# IoT_Week_7.net
KiCad netlist of a schematic drawn in EAGLE
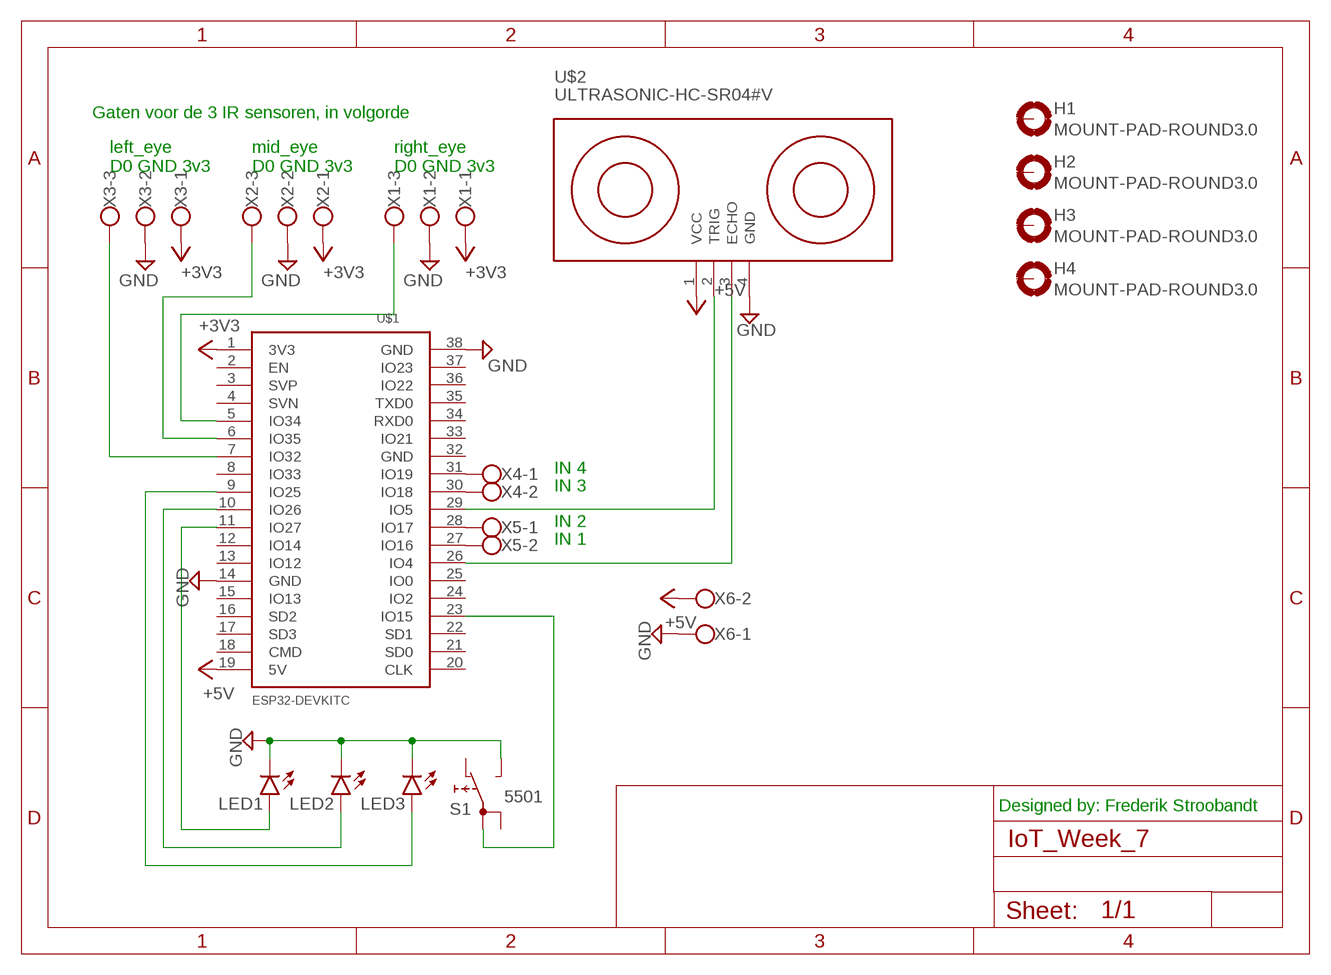
[diagram p0: schematic, sheet 1]

(export (version "E")
  (design (tool "Eeschema 10.0.6"))
  (components
    (comp (ref "H1")
      (value "MOUNT-PAD-ROUND3.0")
      (footprint "eagle-import:3,0-PAD")
      (libsource (lib "eagle-import") (part "MOUNT-PAD-ROUND3.0"))
    )
    (comp (ref "H2")
      (value "MOUNT-PAD-ROUND3.0")
      (footprint "eagle-import:3,0-PAD")
      (libsource (lib "eagle-import") (part "MOUNT-PAD-ROUND3.0"))
    )
    (comp (ref "H3")
      (value "MOUNT-PAD-ROUND3.0")
      (footprint "eagle-import:3,0-PAD")
      (libsource (lib "eagle-import") (part "MOUNT-PAD-ROUND3.0"))
    )
    (comp (ref "H4")
      (value "MOUNT-PAD-ROUND3.0")
      (footprint "eagle-import:3,0-PAD")
      (libsource (lib "eagle-import") (part "MOUNT-PAD-ROUND3.0"))
    )
    (comp (ref "LED1")
      (value "LAP4-BOTTOM")
      (footprint "eagle-import:P47F-BOTTOM")
      (libsource (lib "eagle-import") (part "P4-BOTTOMLA"))
    )
    (comp (ref "LED2")
      (value "LAP4-BOTTOM")
      (footprint "eagle-import:P47F-BOTTOM")
      (libsource (lib "eagle-import") (part "P4-BOTTOMLA"))
    )
    (comp (ref "LED3")
      (value "LAP4-BOTTOM")
      (footprint "eagle-import:P47F-BOTTOM")
      (libsource (lib "eagle-import") (part "P4-BOTTOMLA"))
    )
    (comp (ref "S1")
      (value "5501")
      (footprint "eagle-import:5501")
      (libsource (lib "eagle-import") (part "55?01"))
    )
    (comp (ref "U$1")
      (value "ESP32DEVKITC")
      (footprint "eagle-import:ESP32-DEVKITC")
      (libsource (lib "eagle-import") (part "ESP32DEVKITC"))
    )
    (comp (ref "U$2")
      (value "ULTRASONIC-HC-SR04#V")
      (footprint "eagle-import:ULTRASONIC-HC-SR04#V")
      (libsource (lib "eagle-import") (part "ULTRASONIC-HC-SR04#V"))
    )
    (comp (ref "X1")
      (value "W237-103")
      (footprint "eagle-import:W237-103")
      (fields (field (name "MPN") "237-103"))
      (libsource (lib "eagle-import") (part "W237-103"))
    )
    (comp (ref "X2")
      (value "W237-103")
      (footprint "eagle-import:W237-103")
      (fields (field (name "MPN") "237-103"))
      (libsource (lib "eagle-import") (part "W237-103"))
    )
    (comp (ref "X3")
      (value "W237-103")
      (footprint "eagle-import:W237-103")
      (fields (field (name "MPN") "237-103"))
      (libsource (lib "eagle-import") (part "W237-103"))
    )
    (comp (ref "X4")
      (value "W237-102")
      (footprint "eagle-import:W237-102")
      (fields (field (name "MPN") "237-102"))
      (libsource (lib "eagle-import") (part "W237-102"))
    )
    (comp (ref "X5")
      (value "W237-102")
      (footprint "eagle-import:W237-102")
      (fields (field (name "MPN") "237-102"))
      (libsource (lib "eagle-import") (part "W237-102"))
    )
    (comp (ref "X6")
      (value "W237-102")
      (footprint "eagle-import:W237-102")
      (fields (field (name "MPN") "237-102"))
      (libsource (lib "eagle-import") (part "W237-102"))
    )
  )
  (nets
    (net (code "1") (name "+3V3") (class "Default")
      (node (ref "U$1") (pin "1") (pinfunction "3V3_1") (pintype "bidirectional"))
      (node (ref "X1") (pin "1") (pinfunction "KL_1") (pintype "passive"))
      (node (ref "X2") (pin "1") (pinfunction "KL_1") (pintype "passive"))
      (node (ref "X3") (pin "1") (pinfunction "KL_1") (pintype "passive"))
    )
    (net (code "2") (name "+5V") (class "Default")
      (node (ref "U$1") (pin "19") (pinfunction "5V_19") (pintype "bidirectional"))
      (node (ref "U$2") (pin "1") (pinfunction "VCC_1") (pintype "power_in"))
      (node (ref "X6") (pin "2") (pinfunction "KL_2") (pintype "passive"))
    )
    (net (code "3") (name "GND") (class "Default")
      (node (ref "LED1") (pin "C") (pinfunction "C_C") (pintype "passive"))
      (node (ref "LED2") (pin "C") (pinfunction "C_C") (pintype "passive"))
      (node (ref "LED3") (pin "C") (pinfunction "C_C") (pintype "passive"))
      (node (ref "S1") (pin "NO") (pinfunction "NO_NO") (pintype "passive"))
      (node (ref "U$1") (pin "14") (pinfunction "GND_14") (pintype "bidirectional"))
      (node (ref "U$1") (pin "38") (pinfunction "GND_38") (pintype "bidirectional"))
      (node (ref "U$2") (pin "4") (pinfunction "GND_4") (pintype "power_in"))
      (node (ref "X1") (pin "2") (pinfunction "KL_2") (pintype "passive"))
      (node (ref "X2") (pin "2") (pinfunction "KL_2") (pintype "passive"))
      (node (ref "X3") (pin "2") (pinfunction "KL_2") (pintype "passive"))
      (node (ref "X6") (pin "1") (pinfunction "KL_1") (pintype "passive"))
    )
    (net (code "4") (name "Net-(U$1-IO4)") (class "Default")
      (node (ref "U$1") (pin "26") (pinfunction "IO4_26") (pintype "bidirectional"))
      (node (ref "U$2") (pin "3") (pinfunction "ECHO_3") (pintype "output"))
    )
    (net (code "5") (name "Net-(U$1-IO5)") (class "Default")
      (node (ref "U$1") (pin "29") (pinfunction "IO5_29") (pintype "bidirectional"))
      (node (ref "U$2") (pin "2") (pinfunction "TRIG_2") (pintype "input"))
    )
    (net (code "6") (name "Net-(U$1-IO15)") (class "Default")
      (node (ref "S1") (pin "1A") (pinfunction "1A_1A") (pintype "passive"))
      (node (ref "U$1") (pin "23") (pinfunction "IO15_23") (pintype "bidirectional"))
    )
    (net (code "7") (name "Net-(U$1-IO16)") (class "Default")
      (node (ref "U$1") (pin "27") (pinfunction "IO16_27") (pintype "bidirectional"))
      (node (ref "X5") (pin "2") (pinfunction "KL_2") (pintype "passive"))
    )
    (net (code "8") (name "Net-(U$1-IO17)") (class "Default")
      (node (ref "U$1") (pin "28") (pinfunction "IO17_28") (pintype "bidirectional"))
      (node (ref "X5") (pin "1") (pinfunction "KL_1") (pintype "passive"))
    )
    (net (code "9") (name "Net-(U$1-IO18)") (class "Default")
      (node (ref "U$1") (pin "30") (pinfunction "IO18_30") (pintype "bidirectional"))
      (node (ref "X4") (pin "2") (pinfunction "KL_2") (pintype "passive"))
    )
    (net (code "10") (name "Net-(U$1-IO19)") (class "Default")
      (node (ref "U$1") (pin "31") (pinfunction "IO19_31") (pintype "bidirectional"))
      (node (ref "X4") (pin "1") (pinfunction "KL_1") (pintype "passive"))
    )
    (net (code "11") (name "Net-(U$1-IO25)") (class "Default")
      (node (ref "LED3") (pin "A") (pinfunction "A_A") (pintype "passive"))
      (node (ref "U$1") (pin "9") (pinfunction "IO25_9") (pintype "bidirectional"))
    )
    (net (code "12") (name "Net-(U$1-IO26)") (class "Default")
      (node (ref "LED2") (pin "A") (pinfunction "A_A") (pintype "passive"))
      (node (ref "U$1") (pin "10") (pinfunction "IO26_10") (pintype "bidirectional"))
    )
    (net (code "13") (name "Net-(U$1-IO27)") (class "Default")
      (node (ref "LED1") (pin "A") (pinfunction "A_A") (pintype "passive"))
      (node (ref "U$1") (pin "11") (pinfunction "IO27_11") (pintype "bidirectional"))
    )
    (net (code "14") (name "Net-(U$1-IO32)") (class "Default")
      (node (ref "U$1") (pin "7") (pinfunction "IO32_7") (pintype "bidirectional"))
      (node (ref "X3") (pin "3") (pinfunction "KL_3") (pintype "passive"))
    )
    (net (code "15") (name "Net-(U$1-IO34)") (class "Default")
      (node (ref "U$1") (pin "5") (pinfunction "IO34_5") (pintype "bidirectional"))
      (node (ref "X1") (pin "3") (pinfunction "KL_3") (pintype "passive"))
    )
    (net (code "16") (name "Net-(U$1-IO35)") (class "Default")
      (node (ref "U$1") (pin "6") (pinfunction "IO35_6") (pintype "bidirectional"))
      (node (ref "X2") (pin "3") (pinfunction "KL_3") (pintype "passive"))
    )
    (net (code "17") (name "unconnected-(H1-MOUNT-PadB3,0)") (class "Default")
      (node (ref "H1") (pin "B3,0") (pinfunction "MOUNT_B3,0") (pintype "passive"))
    )
    (net (code "18") (name "unconnected-(H2-MOUNT-PadB3,0)") (class "Default")
      (node (ref "H2") (pin "B3,0") (pinfunction "MOUNT_B3,0") (pintype "passive"))
    )
    (net (code "19") (name "unconnected-(H3-MOUNT-PadB3,0)") (class "Default")
      (node (ref "H3") (pin "B3,0") (pinfunction "MOUNT_B3,0") (pintype "passive"))
    )
    (net (code "20") (name "unconnected-(H4-MOUNT-PadB3,0)") (class "Default")
      (node (ref "H4") (pin "B3,0") (pinfunction "MOUNT_B3,0") (pintype "passive"))
    )
    (net (code "21") (name "unconnected-(S1-Pad1B)") (class "Default")
      (node (ref "S1") (pin "1B") (pinfunction "1B_1B") (pintype "passive"))
    )
    (net (code "22") (name "unconnected-(S1-PadNC)") (class "Default")
      (node (ref "S1") (pin "NC") (pinfunction "NC_NC") (pintype "passive"))
    )
    (net (code "23") (name "unconnected-(U$1-CLK-Pad20)") (class "Default")
      (node (ref "U$1") (pin "20") (pinfunction "CLK_20") (pintype "bidirectional"))
    )
    (net (code "24") (name "unconnected-(U$1-CMD-Pad18)") (class "Default")
      (node (ref "U$1") (pin "18") (pinfunction "CMD_18") (pintype "bidirectional"))
    )
    (net (code "25") (name "unconnected-(U$1-EN-Pad2)") (class "Default")
      (node (ref "U$1") (pin "2") (pinfunction "EN_2") (pintype "bidirectional"))
    )
    (net (code "26") (name "unconnected-(U$1-GND-Pad32)") (class "Default")
      (node (ref "U$1") (pin "32") (pinfunction "GND_32") (pintype "bidirectional"))
    )
    (net (code "27") (name "unconnected-(U$1-IO0-Pad25)") (class "Default")
      (node (ref "U$1") (pin "25") (pinfunction "IO0_25") (pintype "bidirectional"))
    )
    (net (code "28") (name "unconnected-(U$1-IO2-Pad24)") (class "Default")
      (node (ref "U$1") (pin "24") (pinfunction "IO2_24") (pintype "bidirectional"))
    )
    (net (code "29") (name "unconnected-(U$1-IO12-Pad13)") (class "Default")
      (node (ref "U$1") (pin "13") (pinfunction "IO12_13") (pintype "bidirectional"))
    )
    (net (code "30") (name "unconnected-(U$1-IO13-Pad15)") (class "Default")
      (node (ref "U$1") (pin "15") (pinfunction "IO13_15") (pintype "bidirectional"))
    )
    (net (code "31") (name "unconnected-(U$1-IO14-Pad12)") (class "Default")
      (node (ref "U$1") (pin "12") (pinfunction "IO14_12") (pintype "bidirectional"))
    )
    (net (code "32") (name "unconnected-(U$1-IO21-Pad33)") (class "Default")
      (node (ref "U$1") (pin "33") (pinfunction "IO21_33") (pintype "bidirectional"))
    )
    (net (code "33") (name "unconnected-(U$1-IO22-Pad36)") (class "Default")
      (node (ref "U$1") (pin "36") (pinfunction "IO22_36") (pintype "bidirectional"))
    )
    (net (code "34") (name "unconnected-(U$1-IO23-Pad37)") (class "Default")
      (node (ref "U$1") (pin "37") (pinfunction "IO23_37") (pintype "bidirectional"))
    )
    (net (code "35") (name "unconnected-(U$1-IO33-Pad8)") (class "Default")
      (node (ref "U$1") (pin "8") (pinfunction "IO33_8") (pintype "bidirectional"))
    )
    (net (code "36") (name "unconnected-(U$1-RXD0-Pad34)") (class "Default")
      (node (ref "U$1") (pin "34") (pinfunction "RXD0_34") (pintype "bidirectional"))
    )
    (net (code "37") (name "unconnected-(U$1-SD0-Pad21)") (class "Default")
      (node (ref "U$1") (pin "21") (pinfunction "SD0_21") (pintype "bidirectional"))
    )
    (net (code "38") (name "unconnected-(U$1-SD1-Pad22)") (class "Default")
      (node (ref "U$1") (pin "22") (pinfunction "SD1_22") (pintype "bidirectional"))
    )
    (net (code "39") (name "unconnected-(U$1-SD2-Pad16)") (class "Default")
      (node (ref "U$1") (pin "16") (pinfunction "SD2_16") (pintype "bidirectional"))
    )
    (net (code "40") (name "unconnected-(U$1-SD3-Pad17)") (class "Default")
      (node (ref "U$1") (pin "17") (pinfunction "SD3_17") (pintype "bidirectional"))
    )
    (net (code "41") (name "unconnected-(U$1-SVN-Pad4)") (class "Default")
      (node (ref "U$1") (pin "4") (pinfunction "SVN_4") (pintype "bidirectional"))
    )
    (net (code "42") (name "unconnected-(U$1-SVP-Pad3)") (class "Default")
      (node (ref "U$1") (pin "3") (pinfunction "SVP_3") (pintype "bidirectional"))
    )
    (net (code "43") (name "unconnected-(U$1-TXD0-Pad35)") (class "Default")
      (node (ref "U$1") (pin "35") (pinfunction "TXD0_35") (pintype "bidirectional"))
    )
  )
)
